# Sheet1.net
KiCad netlist of a schematic drawn in Altium Designer
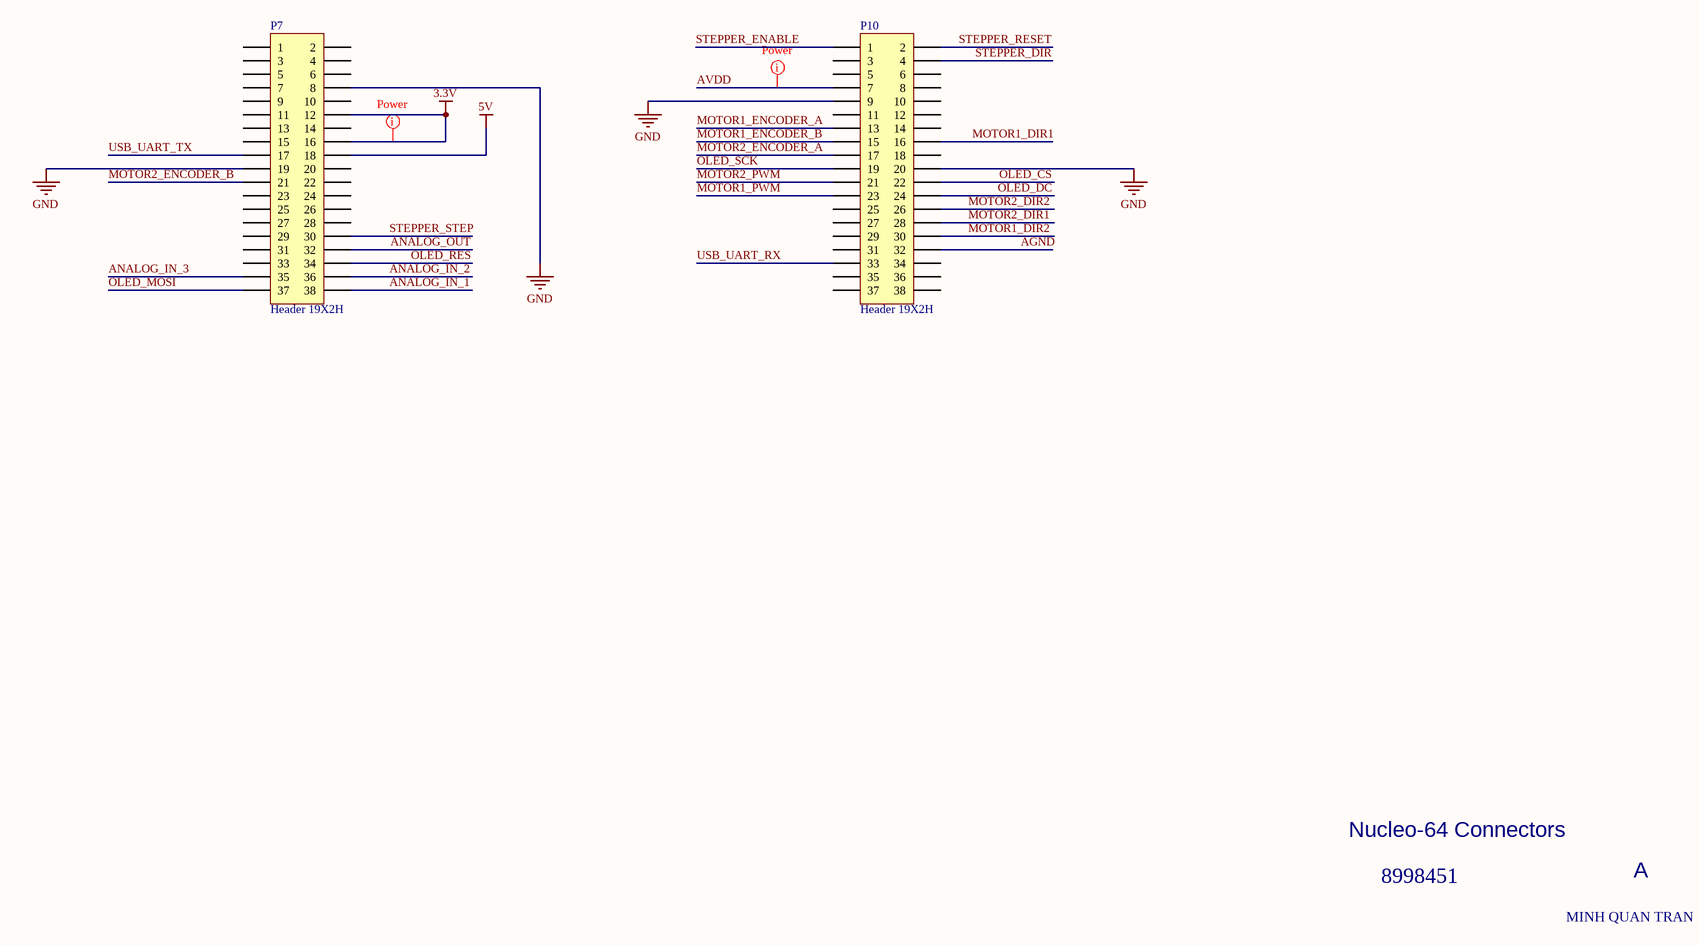
[diagram p0: Sheet1.SchDoc]

(export (version "E")
  (design (tool "Eeschema 10.0.6"))
  (components
    (comp (ref "P7")
      (value "Header 19X2H")
      (footprint "PPPC192LFBN-RC")
      (description "38 Position Header Connector 0.100in (2.54mm) Through Hole Gold")
      (fields (field (name "MPN") "PPPC192LFBN-RC"))
      (libsource (lib "esd_library") (part "Header 19X2H"))
    )
    (comp (ref "P10")
      (value "Header 19X2H")
      (footprint "PPPC192LFBN-RC")
      (description "38 Position Header Connector 0.100in (2.54mm) Through Hole Gold")
      (fields (field (name "MPN") "PPPC192LFBN-RC"))
      (libsource (lib "esd_library") (part "Header 19X2H"))
    )
  )
  (nets
    (net (code "1") (name "/AGND") (class "Default")
      (node (ref "P10") (pin "32") (pinfunction "32_32") (pintype "passive"))
    )
    (net (code "2") (name "/ANALOG_IN_1") (class "Default")
      (node (ref "P7") (pin "38") (pinfunction "38_38") (pintype "passive"))
    )
    (net (code "3") (name "/ANALOG_IN_2") (class "Default")
      (node (ref "P7") (pin "36") (pinfunction "36_36") (pintype "passive"))
    )
    (net (code "4") (name "/ANALOG_IN_3") (class "Default")
      (node (ref "P7") (pin "35") (pinfunction "35_35") (pintype "passive"))
    )
    (net (code "5") (name "/ANALOG_OUT") (class "Default")
      (node (ref "P7") (pin "32") (pinfunction "32_32") (pintype "passive"))
    )
    (net (code "6") (name "/AVDD") (class "Default")
      (node (ref "P10") (pin "7") (pinfunction "7_7") (pintype "passive"))
    )
    (net (code "7") (name "/MOTOR1_DIR1") (class "Default")
      (node (ref "P10") (pin "16") (pinfunction "16_16") (pintype "passive"))
    )
    (net (code "8") (name "/MOTOR1_DIR2") (class "Default")
      (node (ref "P10") (pin "30") (pinfunction "30_30") (pintype "passive"))
    )
    (net (code "9") (name "/MOTOR1_ENCODER_A") (class "Default")
      (node (ref "P10") (pin "13") (pinfunction "13_13") (pintype "passive"))
    )
    (net (code "10") (name "/MOTOR1_ENCODER_B") (class "Default")
      (node (ref "P10") (pin "15") (pinfunction "15_15") (pintype "passive"))
    )
    (net (code "11") (name "/MOTOR1_PWM") (class "Default")
      (node (ref "P10") (pin "23") (pinfunction "23_23") (pintype "passive"))
    )
    (net (code "12") (name "/MOTOR2_DIR1") (class "Default")
      (node (ref "P10") (pin "28") (pinfunction "28_28") (pintype "passive"))
    )
    (net (code "13") (name "/MOTOR2_DIR2") (class "Default")
      (node (ref "P10") (pin "26") (pinfunction "26_26") (pintype "passive"))
    )
    (net (code "14") (name "/MOTOR2_ENCODER_A") (class "Default")
      (node (ref "P10") (pin "17") (pinfunction "17_17") (pintype "passive"))
    )
    (net (code "15") (name "/MOTOR2_ENCODER_B") (class "Default")
      (node (ref "P7") (pin "21") (pinfunction "21_21") (pintype "passive"))
    )
    (net (code "16") (name "/MOTOR2_PWM") (class "Default")
      (node (ref "P10") (pin "21") (pinfunction "21_21") (pintype "passive"))
    )
    (net (code "17") (name "/OLED_CS") (class "Default")
      (node (ref "P10") (pin "22") (pinfunction "22_22") (pintype "passive"))
    )
    (net (code "18") (name "/OLED_DC") (class "Default")
      (node (ref "P10") (pin "24") (pinfunction "24_24") (pintype "passive"))
    )
    (net (code "19") (name "/OLED_MOSI") (class "Default")
      (node (ref "P7") (pin "37") (pinfunction "37_37") (pintype "passive"))
    )
    (net (code "20") (name "/OLED_RES") (class "Default")
      (node (ref "P7") (pin "34") (pinfunction "34_34") (pintype "passive"))
    )
    (net (code "21") (name "/OLED_SCK") (class "Default")
      (node (ref "P10") (pin "19") (pinfunction "19_19") (pintype "passive"))
    )
    (net (code "22") (name "/STEPPER_DIR") (class "Default")
      (node (ref "P10") (pin "4") (pinfunction "4_4") (pintype "passive"))
    )
    (net (code "23") (name "/STEPPER_ENABLE") (class "Default")
      (node (ref "P10") (pin "1") (pinfunction "1_1") (pintype "passive"))
    )
    (net (code "24") (name "/STEPPER_RESET") (class "Default")
      (node (ref "P10") (pin "2") (pinfunction "2_2") (pintype "passive"))
    )
    (net (code "25") (name "/STEPPER_STEP") (class "Default")
      (node (ref "P7") (pin "30") (pinfunction "30_30") (pintype "passive"))
    )
    (net (code "26") (name "/USB_UART_RX") (class "Default")
      (node (ref "P10") (pin "33") (pinfunction "33_33") (pintype "passive"))
    )
    (net (code "27") (name "/USB_UART_TX") (class "Default")
      (node (ref "P7") (pin "17") (pinfunction "17_17") (pintype "passive"))
    )
    (net (code "28") (name "3.3V") (class "Default")
      (node (ref "P7") (pin "12") (pinfunction "12_12") (pintype "passive"))
      (node (ref "P7") (pin "16") (pinfunction "16_16") (pintype "passive"))
    )
    (net (code "29") (name "5V") (class "Default")
      (node (ref "P7") (pin "18") (pinfunction "18_18") (pintype "passive"))
    )
    (net (code "30") (name "GND") (class "Default")
      (node (ref "P10") (pin "20") (pinfunction "20_20") (pintype "passive"))
      (node (ref "P10") (pin "9") (pinfunction "9_9") (pintype "passive"))
      (node (ref "P7") (pin "19") (pinfunction "19_19") (pintype "passive"))
      (node (ref "P7") (pin "8") (pinfunction "8_8") (pintype "passive"))
    )
    (net (code "31") (name "unconnected-(P7-Pad1)") (class "Default")
      (node (ref "P7") (pin "1") (pinfunction "1_1") (pintype "passive"))
    )
    (net (code "32") (name "unconnected-(P7-Pad2)") (class "Default")
      (node (ref "P7") (pin "2") (pinfunction "2_2") (pintype "passive"))
    )
    (net (code "33") (name "unconnected-(P7-Pad3)") (class "Default")
      (node (ref "P7") (pin "3") (pinfunction "3_3") (pintype "passive"))
    )
    (net (code "34") (name "unconnected-(P7-Pad4)") (class "Default")
      (node (ref "P7") (pin "4") (pinfunction "4_4") (pintype "passive"))
    )
    (net (code "35") (name "unconnected-(P7-Pad5)") (class "Default")
      (node (ref "P7") (pin "5") (pinfunction "5_5") (pintype "passive"))
    )
    (net (code "36") (name "unconnected-(P7-Pad6)") (class "Default")
      (node (ref "P7") (pin "6") (pinfunction "6_6") (pintype "passive"))
    )
    (net (code "37") (name "unconnected-(P7-Pad7)") (class "Default")
      (node (ref "P7") (pin "7") (pinfunction "7_7") (pintype "passive"))
    )
    (net (code "38") (name "unconnected-(P7-Pad9)") (class "Default")
      (node (ref "P7") (pin "9") (pinfunction "9_9") (pintype "passive"))
    )
    (net (code "39") (name "unconnected-(P7-Pad10)") (class "Default")
      (node (ref "P7") (pin "10") (pinfunction "10_10") (pintype "passive"))
    )
    (net (code "40") (name "unconnected-(P7-Pad11)") (class "Default")
      (node (ref "P7") (pin "11") (pinfunction "11_11") (pintype "passive"))
    )
    (net (code "41") (name "unconnected-(P7-Pad13)") (class "Default")
      (node (ref "P7") (pin "13") (pinfunction "13_13") (pintype "passive"))
    )
    (net (code "42") (name "unconnected-(P7-Pad14)") (class "Default")
      (node (ref "P7") (pin "14") (pinfunction "14_14") (pintype "passive"))
    )
    (net (code "43") (name "unconnected-(P7-Pad15)") (class "Default")
      (node (ref "P7") (pin "15") (pinfunction "15_15") (pintype "passive"))
    )
    (net (code "44") (name "unconnected-(P7-Pad20)") (class "Default")
      (node (ref "P7") (pin "20") (pinfunction "20_20") (pintype "passive"))
    )
    (net (code "45") (name "unconnected-(P7-Pad22)") (class "Default")
      (node (ref "P7") (pin "22") (pinfunction "22_22") (pintype "passive"))
    )
    (net (code "46") (name "unconnected-(P7-Pad23)") (class "Default")
      (node (ref "P7") (pin "23") (pinfunction "23_23") (pintype "passive"))
    )
    (net (code "47") (name "unconnected-(P7-Pad24)") (class "Default")
      (node (ref "P7") (pin "24") (pinfunction "24_24") (pintype "passive"))
    )
    (net (code "48") (name "unconnected-(P7-Pad25)") (class "Default")
      (node (ref "P7") (pin "25") (pinfunction "25_25") (pintype "passive"))
    )
    (net (code "49") (name "unconnected-(P7-Pad26)") (class "Default")
      (node (ref "P7") (pin "26") (pinfunction "26_26") (pintype "passive"))
    )
    (net (code "50") (name "unconnected-(P7-Pad27)") (class "Default")
      (node (ref "P7") (pin "27") (pinfunction "27_27") (pintype "passive"))
    )
    (net (code "51") (name "unconnected-(P7-Pad28)") (class "Default")
      (node (ref "P7") (pin "28") (pinfunction "28_28") (pintype "passive"))
    )
    (net (code "52") (name "unconnected-(P7-Pad29)") (class "Default")
      (node (ref "P7") (pin "29") (pinfunction "29_29") (pintype "passive"))
    )
    (net (code "53") (name "unconnected-(P7-Pad31)") (class "Default")
      (node (ref "P7") (pin "31") (pinfunction "31_31") (pintype "passive"))
    )
    (net (code "54") (name "unconnected-(P7-Pad33)") (class "Default")
      (node (ref "P7") (pin "33") (pinfunction "33_33") (pintype "passive"))
    )
    (net (code "55") (name "unconnected-(P10-Pad3)") (class "Default")
      (node (ref "P10") (pin "3") (pinfunction "3_3") (pintype "passive"))
    )
    (net (code "56") (name "unconnected-(P10-Pad5)") (class "Default")
      (node (ref "P10") (pin "5") (pinfunction "5_5") (pintype "passive"))
    )
    (net (code "57") (name "unconnected-(P10-Pad6)") (class "Default")
      (node (ref "P10") (pin "6") (pinfunction "6_6") (pintype "passive"))
    )
    (net (code "58") (name "unconnected-(P10-Pad8)") (class "Default")
      (node (ref "P10") (pin "8") (pinfunction "8_8") (pintype "passive"))
    )
    (net (code "59") (name "unconnected-(P10-Pad10)") (class "Default")
      (node (ref "P10") (pin "10") (pinfunction "10_10") (pintype "passive"))
    )
    (net (code "60") (name "unconnected-(P10-Pad11)") (class "Default")
      (node (ref "P10") (pin "11") (pinfunction "11_11") (pintype "passive"))
    )
    (net (code "61") (name "unconnected-(P10-Pad12)") (class "Default")
      (node (ref "P10") (pin "12") (pinfunction "12_12") (pintype "passive"))
    )
    (net (code "62") (name "unconnected-(P10-Pad14)") (class "Default")
      (node (ref "P10") (pin "14") (pinfunction "14_14") (pintype "passive"))
    )
    (net (code "63") (name "unconnected-(P10-Pad18)") (class "Default")
      (node (ref "P10") (pin "18") (pinfunction "18_18") (pintype "passive"))
    )
    (net (code "64") (name "unconnected-(P10-Pad25)") (class "Default")
      (node (ref "P10") (pin "25") (pinfunction "25_25") (pintype "passive"))
    )
    (net (code "65") (name "unconnected-(P10-Pad27)") (class "Default")
      (node (ref "P10") (pin "27") (pinfunction "27_27") (pintype "passive"))
    )
    (net (code "66") (name "unconnected-(P10-Pad29)") (class "Default")
      (node (ref "P10") (pin "29") (pinfunction "29_29") (pintype "passive"))
    )
    (net (code "67") (name "unconnected-(P10-Pad31)") (class "Default")
      (node (ref "P10") (pin "31") (pinfunction "31_31") (pintype "passive"))
    )
    (net (code "68") (name "unconnected-(P10-Pad34)") (class "Default")
      (node (ref "P10") (pin "34") (pinfunction "34_34") (pintype "passive"))
    )
    (net (code "69") (name "unconnected-(P10-Pad35)") (class "Default")
      (node (ref "P10") (pin "35") (pinfunction "35_35") (pintype "passive"))
    )
    (net (code "70") (name "unconnected-(P10-Pad36)") (class "Default")
      (node (ref "P10") (pin "36") (pinfunction "36_36") (pintype "passive"))
    )
    (net (code "71") (name "unconnected-(P10-Pad37)") (class "Default")
      (node (ref "P10") (pin "37") (pinfunction "37_37") (pintype "passive"))
    )
    (net (code "72") (name "unconnected-(P10-Pad38)") (class "Default")
      (node (ref "P10") (pin "38") (pinfunction "38_38") (pintype "passive"))
    )
  )
)
